# TRS-80_Testboard.net
KiCad netlist of a schematic drawn in EasyEDA
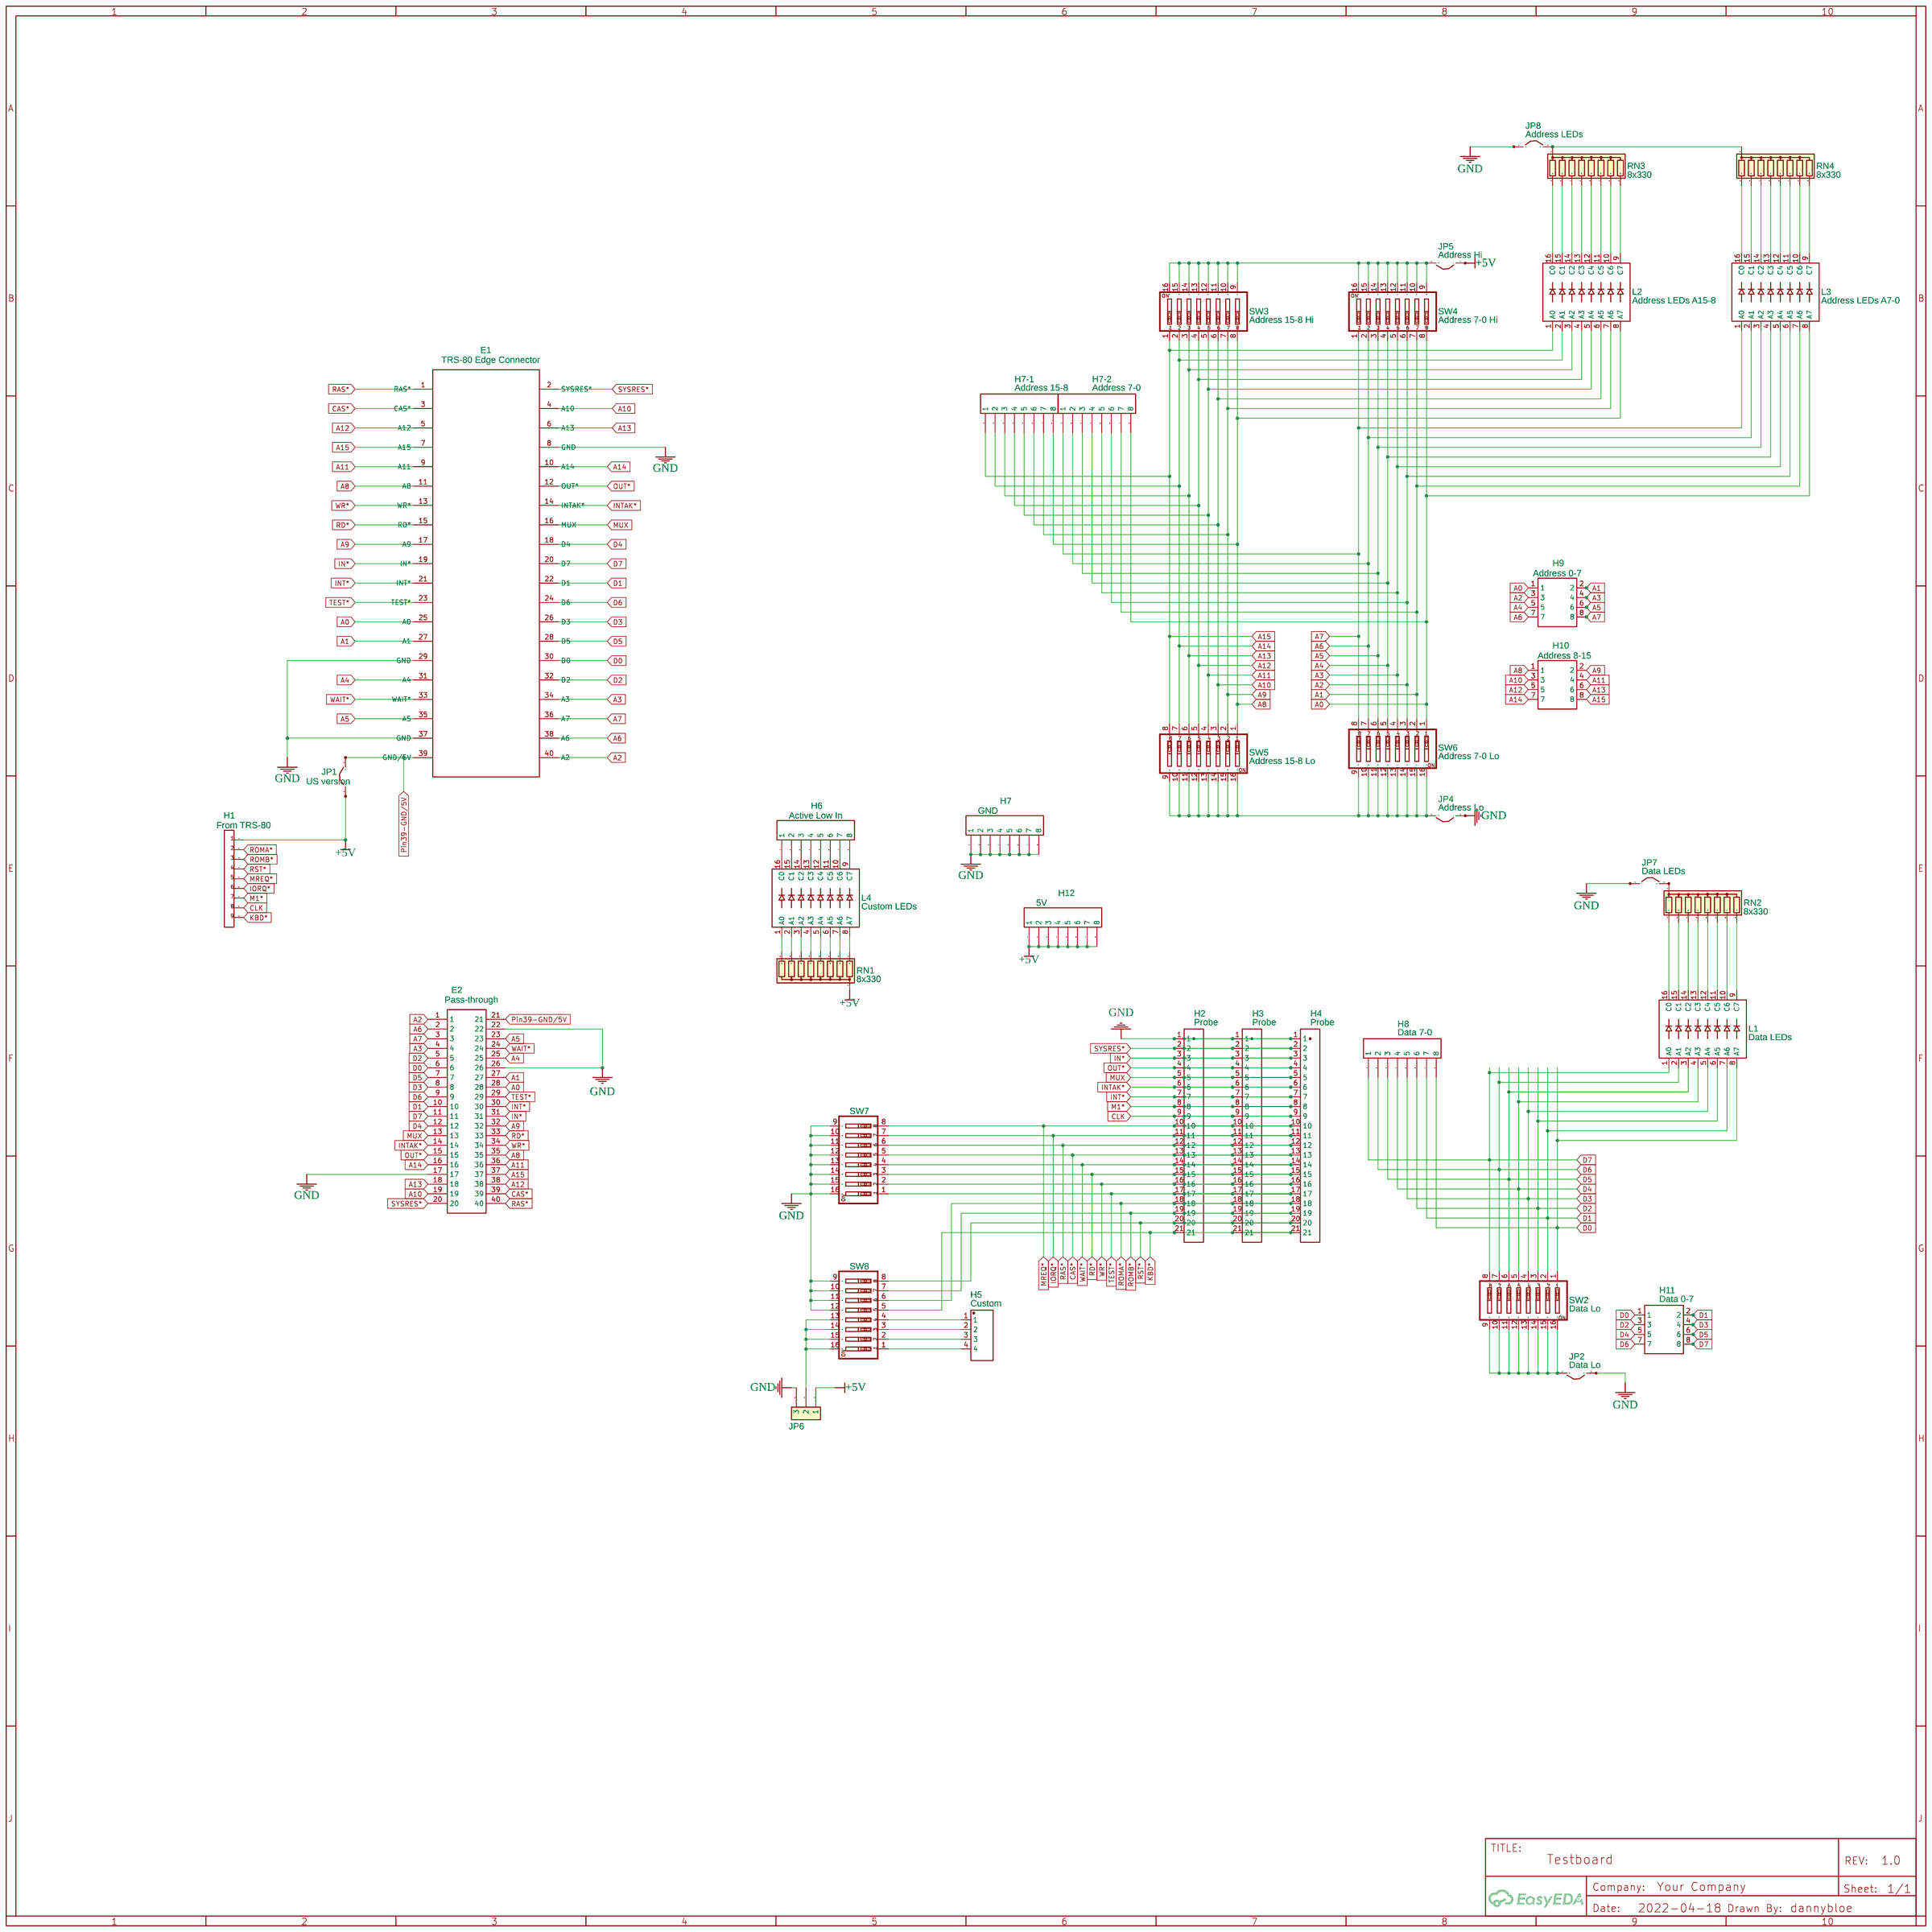
[diagram p0: schematic sheet]

(export (version "E")
  (design (tool "Eeschema 10.0.6"))
  (components
    (comp (ref "E1") (value "TRS-80 Edge Connector") (libsource (lib "") (part "TRS-80 Edge Connector")))
    (comp (ref "E2") (value "Pass-through") (libsource (lib "") (part "40-pos Edge Connector")))
    (comp (ref "H1") (value "From TRS-80") (libsource (lib "") (part "Header1x9_2.54")))
    (comp (ref "H2") (value "Probe") (libsource (lib "") (part "Header 21pin")))
    (comp (ref "H3") (value "Probe") (libsource (lib "") (part "Header 21pin")))
    (comp (ref "H4") (value "Probe") (libsource (lib "") (part "Header 21pin")))
    (comp (ref "H5") (value "Custom") (libsource (lib "") (part "HEADER - HEADER-FEMALE-2.54_1X4")))
    (comp (ref "H6")
      (value "Active Low In")
      (fields
        (field (name "BOM_Manufacturer Part") "Header2.54mm 1*8P")
        (field (name "BOM_Supplier Part") "C49256")
      )
      (libsource (lib "") (part "Header2.54mm 1*8P"))
    )
    (comp (ref "H7")
      (value "GND")
      (fields
        (field (name "BOM_Manufacturer Part") "Header2.54mm 1*8P")
        (field (name "BOM_Supplier Part") "C49256")
      )
      (libsource (lib "") (part "Header2.54mm 1*8P"))
    )
    (comp (ref "H7-1")
      (value "Address 15-8")
      (fields
        (field (name "BOM_Manufacturer Part") "Header2.54mm 1*8P")
        (field (name "BOM_Supplier Part") "C49256")
      )
      (libsource (lib "") (part "Header2.54mm 1*8P_1"))
    )
    (comp (ref "H7-2")
      (value "Address 7-0")
      (fields
        (field (name "BOM_Manufacturer Part") "Header2.54mm 1*8P")
        (field (name "BOM_Supplier Part") "C49256")
      )
      (libsource (lib "") (part "Header2.54mm 1*8P_1"))
    )
    (comp (ref "H8")
      (value "Data 7-0")
      (fields
        (field (name "BOM_Manufacturer Part") "Header2.54mm 1*8P")
        (field (name "BOM_Supplier Part") "C49256")
      )
      (libsource (lib "") (part "Header2.54mm 1*8P"))
    )
    (comp (ref "H9")
      (value "Address 0-7")
      (fields (field (name "BOM_Manufacturer Part") "BKL 10120552"))
      (libsource (lib "") (part "Box Header 8P"))
    )
    (comp (ref "H10")
      (value "Address 8-15")
      (fields (field (name "BOM_Manufacturer Part") "BKL 10120552"))
      (libsource (lib "") (part "Box Header 8P"))
    )
    (comp (ref "H11")
      (value "Data 0-7")
      (fields (field (name "BOM_Manufacturer Part") "BKL 10120552"))
      (libsource (lib "") (part "Box Header 8P"))
    )
    (comp (ref "H12")
      (value "5V")
      (fields
        (field (name "BOM_Manufacturer Part") "Header2.54mm 1*8P")
        (field (name "BOM_Supplier Part") "C49256")
      )
      (libsource (lib "") (part "Header2.54mm 1*8P"))
    )
    (comp (ref "JP1")
      (value "US version")
      (fields (field (name "BOM_Manufacturer Part") "NONE"))
      (libsource (lib "") (part "JUMPERTHRUHOLE_1"))
    )
    (comp (ref "JP2")
      (value "Data Lo")
      (fields (field (name "BOM_Manufacturer Part") "NONE"))
      (libsource (lib "") (part "JUMPERTHRUHOLE_2"))
    )
    (comp (ref "JP4")
      (value "Address Lo")
      (fields (field (name "BOM_Manufacturer Part") "NONE"))
      (libsource (lib "") (part "JUMPERTHRUHOLE_2"))
    )
    (comp (ref "JP5")
      (value "Address Hi")
      (fields (field (name "BOM_Manufacturer Part") "NONE"))
      (libsource (lib "") (part "JUMPERTHRUHOLE_2"))
    )
    (comp (ref "JP6")
      (value "Header1x3")
      (fields
        (field (name "BOM_Manufacturer Part") "Header-Female-2.54_1x10")
        (field (name "BOM_Supplier Part") "C35445")
      )
      (libsource (lib "") (part "Header1x3"))
    )
    (comp (ref "JP7")
      (value "Data LEDs")
      (fields (field (name "BOM_Manufacturer Part") "NONE"))
      (libsource (lib "") (part "JUMPERTHRUHOLE"))
    )
    (comp (ref "JP8")
      (value "Address LEDs")
      (fields (field (name "BOM_Manufacturer Part") "NONE"))
      (libsource (lib "") (part "JUMPERTHRUHOLE"))
    )
    (comp (ref "L1") (value "Data LEDs") (libsource (lib "") (part "BARGRAPH_8")))
    (comp (ref "L2") (value "Address LEDs A15-8") (libsource (lib "") (part "BARGRAPH_8")))
    (comp (ref "L3") (value "Address LEDs A7-0") (libsource (lib "") (part "BARGRAPH_8")))
    (comp (ref "L4") (value "Custom LEDs") (libsource (lib "") (part "BARGRAPH_8")))
    (comp (ref "RN1") (value "8x330") (libsource (lib "") (part "Resistor Network 8")))
    (comp (ref "RN2") (value "8x330") (libsource (lib "") (part "Resistor Network 8_1")))
    (comp (ref "RN3") (value "8x330") (libsource (lib "") (part "Resistor Network 8_1")))
    (comp (ref "RN4") (value "8x330") (libsource (lib "") (part "Resistor Network 8_1")))
    (comp (ref "SW2") (value "Data Lo") (libsource (lib "") (part "SW_DIP-8_3")))
    (comp (ref "SW3") (value "Address 15-8 Hi") (libsource (lib "") (part "SW_DIP-8_2")))
    (comp (ref "SW4") (value "Address 7-0 Hi") (libsource (lib "") (part "SW_DIP-8_2")))
    (comp (ref "SW5") (value "Address 15-8 Lo") (libsource (lib "") (part "SW_DIP-8")))
    (comp (ref "SW6") (value "Address 7-0 Lo") (libsource (lib "") (part "SW_DIP-8")))
    (comp (ref "SW7") (value "Switches") (libsource (lib "") (part "SW_DIP-8_1")))
    (comp (ref "SW8") (value "Switches") (libsource (lib "") (part "SW_DIP-8_1")))
  )
  (nets
    (net (code "1") (name "+5V") (class "Default")
      (node (ref "H1") (pin "1") (pinfunction "1_1") (pintype "unspecified"))
      (node (ref "H12") (pin "1") (pinfunction "1_1") (pintype "input"))
      (node (ref "H12") (pin "2") (pinfunction "2_2") (pintype "input"))
      (node (ref "H12") (pin "3") (pinfunction "3_3") (pintype "input"))
      (node (ref "H12") (pin "4") (pinfunction "4_4") (pintype "input"))
      (node (ref "H12") (pin "5") (pinfunction "5_5") (pintype "input"))
      (node (ref "H12") (pin "6") (pinfunction "6_6") (pintype "input"))
      (node (ref "H12") (pin "7") (pinfunction "7_7") (pintype "input"))
      (node (ref "H12") (pin "8") (pinfunction "8_8") (pintype "input"))
      (node (ref "JP1") (pin "1") (pinfunction "1_1") (pintype "unspecified"))
      (node (ref "JP5") (pin "1") (pinfunction "1_1") (pintype "unspecified"))
      (node (ref "JP6") (pin "1") (pinfunction "1_1") (pintype "input"))
      (node (ref "RN1") (pin "1") (pinfunction "common_1") (pintype "unspecified"))
    )
    (net (code "2") (name "A0") (class "Default")
      (node (ref "E1") (pin "25") (pinfunction "A0_25") (pintype "unspecified"))
      (node (ref "E2") (pin "28") (pinfunction "28_28") (pintype "unspecified"))
      (node (ref "H7-2") (pin "8") (pinfunction "8_8") (pintype "input"))
      (node (ref "H9") (pin "1") (pinfunction "1_1") (pintype "unspecified"))
      (node (ref "L3") (pin "8") (pinfunction "A7_8") (pintype "unspecified"))
      (node (ref "SW4") (pin "8") (pinfunction "8_8") (pintype "bidirectional"))
      (node (ref "SW6") (pin "1") (pinfunction "1_1") (pintype "bidirectional"))
    )
    (net (code "3") (name "A1") (class "Default")
      (node (ref "E1") (pin "27") (pinfunction "A1_27") (pintype "unspecified"))
      (node (ref "E2") (pin "27") (pinfunction "27_27") (pintype "unspecified"))
      (node (ref "H7-2") (pin "7") (pinfunction "7_7") (pintype "input"))
      (node (ref "H9") (pin "2") (pinfunction "2_2") (pintype "unspecified"))
      (node (ref "L3") (pin "7") (pinfunction "A6_7") (pintype "unspecified"))
      (node (ref "SW4") (pin "7") (pinfunction "7_7") (pintype "bidirectional"))
      (node (ref "SW6") (pin "2") (pinfunction "2_2") (pintype "bidirectional"))
    )
    (net (code "4") (name "A2") (class "Default")
      (node (ref "E1") (pin "40") (pinfunction "A2_40") (pintype "unspecified"))
      (node (ref "E2") (pin "1") (pinfunction "1_1") (pintype "unspecified"))
      (node (ref "H7-2") (pin "6") (pinfunction "6_6") (pintype "input"))
      (node (ref "H9") (pin "3") (pinfunction "3_3") (pintype "unspecified"))
      (node (ref "L3") (pin "6") (pinfunction "A5_6") (pintype "unspecified"))
      (node (ref "SW4") (pin "6") (pinfunction "6_6") (pintype "bidirectional"))
      (node (ref "SW6") (pin "3") (pinfunction "3_3") (pintype "bidirectional"))
    )
    (net (code "5") (name "A3") (class "Default")
      (node (ref "E1") (pin "34") (pinfunction "A3_34") (pintype "unspecified"))
      (node (ref "E2") (pin "4") (pinfunction "4_4") (pintype "unspecified"))
      (node (ref "H7-2") (pin "5") (pinfunction "5_5") (pintype "input"))
      (node (ref "H9") (pin "4") (pinfunction "4_4") (pintype "unspecified"))
      (node (ref "L3") (pin "5") (pinfunction "A4_5") (pintype "unspecified"))
      (node (ref "SW4") (pin "5") (pinfunction "5_5") (pintype "bidirectional"))
      (node (ref "SW6") (pin "4") (pinfunction "4_4") (pintype "bidirectional"))
    )
    (net (code "6") (name "A4") (class "Default")
      (node (ref "E1") (pin "31") (pinfunction "A4_31") (pintype "unspecified"))
      (node (ref "E2") (pin "25") (pinfunction "25_25") (pintype "unspecified"))
      (node (ref "H7-2") (pin "4") (pinfunction "4_4") (pintype "input"))
      (node (ref "H9") (pin "5") (pinfunction "5_5") (pintype "unspecified"))
      (node (ref "L3") (pin "4") (pinfunction "A3_4") (pintype "unspecified"))
      (node (ref "SW4") (pin "4") (pinfunction "4_4") (pintype "bidirectional"))
      (node (ref "SW6") (pin "5") (pinfunction "5_5") (pintype "bidirectional"))
    )
    (net (code "7") (name "A5") (class "Default")
      (node (ref "E1") (pin "35") (pinfunction "A5_35") (pintype "unspecified"))
      (node (ref "E2") (pin "23") (pinfunction "23_23") (pintype "unspecified"))
      (node (ref "H7-2") (pin "3") (pinfunction "3_3") (pintype "input"))
      (node (ref "H9") (pin "6") (pinfunction "6_6") (pintype "unspecified"))
      (node (ref "L3") (pin "3") (pinfunction "A2_3") (pintype "unspecified"))
      (node (ref "SW4") (pin "3") (pinfunction "3_3") (pintype "bidirectional"))
      (node (ref "SW6") (pin "6") (pinfunction "6_6") (pintype "bidirectional"))
    )
    (net (code "8") (name "A6") (class "Default")
      (node (ref "E1") (pin "38") (pinfunction "A6_38") (pintype "unspecified"))
      (node (ref "E2") (pin "2") (pinfunction "2_2") (pintype "unspecified"))
      (node (ref "H7-2") (pin "2") (pinfunction "2_2") (pintype "input"))
      (node (ref "H9") (pin "7") (pinfunction "7_7") (pintype "unspecified"))
      (node (ref "L3") (pin "2") (pinfunction "A1_2") (pintype "unspecified"))
      (node (ref "SW4") (pin "2") (pinfunction "2_2") (pintype "bidirectional"))
      (node (ref "SW6") (pin "7") (pinfunction "7_7") (pintype "bidirectional"))
    )
    (net (code "9") (name "A7") (class "Default")
      (node (ref "E1") (pin "36") (pinfunction "A7_36") (pintype "unspecified"))
      (node (ref "E2") (pin "3") (pinfunction "3_3") (pintype "unspecified"))
      (node (ref "H7-2") (pin "1") (pinfunction "1_1") (pintype "input"))
      (node (ref "H9") (pin "8") (pinfunction "8_8") (pintype "unspecified"))
      (node (ref "L3") (pin "1") (pinfunction "A0_1") (pintype "unspecified"))
      (node (ref "SW4") (pin "1") (pinfunction "1_1") (pintype "bidirectional"))
      (node (ref "SW6") (pin "8") (pinfunction "8_8") (pintype "bidirectional"))
    )
    (net (code "10") (name "A8") (class "Default")
      (node (ref "E1") (pin "11") (pinfunction "A8_11") (pintype "unspecified"))
      (node (ref "E2") (pin "35") (pinfunction "35_35") (pintype "unspecified"))
      (node (ref "H10") (pin "1") (pinfunction "1_1") (pintype "unspecified"))
      (node (ref "H7-1") (pin "8") (pinfunction "8_8") (pintype "input"))
      (node (ref "L2") (pin "8") (pinfunction "A7_8") (pintype "unspecified"))
      (node (ref "SW3") (pin "8") (pinfunction "8_8") (pintype "bidirectional"))
      (node (ref "SW5") (pin "1") (pinfunction "1_1") (pintype "bidirectional"))
    )
    (net (code "11") (name "A9") (class "Default")
      (node (ref "E1") (pin "17") (pinfunction "A9_17") (pintype "unspecified"))
      (node (ref "E2") (pin "32") (pinfunction "32_32") (pintype "unspecified"))
      (node (ref "H10") (pin "2") (pinfunction "2_2") (pintype "unspecified"))
      (node (ref "H7-1") (pin "7") (pinfunction "7_7") (pintype "input"))
      (node (ref "L2") (pin "7") (pinfunction "A6_7") (pintype "unspecified"))
      (node (ref "SW3") (pin "7") (pinfunction "7_7") (pintype "bidirectional"))
      (node (ref "SW5") (pin "2") (pinfunction "2_2") (pintype "bidirectional"))
    )
    (net (code "12") (name "A10") (class "Default")
      (node (ref "E1") (pin "4") (pinfunction "A10_4") (pintype "unspecified"))
      (node (ref "E2") (pin "19") (pinfunction "19_19") (pintype "unspecified"))
      (node (ref "H10") (pin "3") (pinfunction "3_3") (pintype "unspecified"))
      (node (ref "H7-1") (pin "6") (pinfunction "6_6") (pintype "input"))
      (node (ref "L2") (pin "6") (pinfunction "A5_6") (pintype "unspecified"))
      (node (ref "SW3") (pin "6") (pinfunction "6_6") (pintype "bidirectional"))
      (node (ref "SW5") (pin "3") (pinfunction "3_3") (pintype "bidirectional"))
    )
    (net (code "13") (name "A11") (class "Default")
      (node (ref "E1") (pin "9") (pinfunction "A11_9") (pintype "unspecified"))
      (node (ref "E2") (pin "36") (pinfunction "36_36") (pintype "unspecified"))
      (node (ref "H10") (pin "4") (pinfunction "4_4") (pintype "unspecified"))
      (node (ref "H7-1") (pin "5") (pinfunction "5_5") (pintype "input"))
      (node (ref "L2") (pin "5") (pinfunction "A4_5") (pintype "unspecified"))
      (node (ref "SW3") (pin "5") (pinfunction "5_5") (pintype "bidirectional"))
      (node (ref "SW5") (pin "4") (pinfunction "4_4") (pintype "bidirectional"))
    )
    (net (code "14") (name "A12") (class "Default")
      (node (ref "E1") (pin "5") (pinfunction "A12_5") (pintype "unspecified"))
      (node (ref "E2") (pin "38") (pinfunction "38_38") (pintype "unspecified"))
      (node (ref "H10") (pin "5") (pinfunction "5_5") (pintype "unspecified"))
      (node (ref "H7-1") (pin "4") (pinfunction "4_4") (pintype "input"))
      (node (ref "L2") (pin "4") (pinfunction "A3_4") (pintype "unspecified"))
      (node (ref "SW3") (pin "4") (pinfunction "4_4") (pintype "bidirectional"))
      (node (ref "SW5") (pin "5") (pinfunction "5_5") (pintype "bidirectional"))
    )
    (net (code "15") (name "A13") (class "Default")
      (node (ref "E1") (pin "6") (pinfunction "A13_6") (pintype "unspecified"))
      (node (ref "E2") (pin "18") (pinfunction "18_18") (pintype "unspecified"))
      (node (ref "H10") (pin "6") (pinfunction "6_6") (pintype "unspecified"))
      (node (ref "H7-1") (pin "3") (pinfunction "3_3") (pintype "input"))
      (node (ref "L2") (pin "3") (pinfunction "A2_3") (pintype "unspecified"))
      (node (ref "SW3") (pin "3") (pinfunction "3_3") (pintype "bidirectional"))
      (node (ref "SW5") (pin "6") (pinfunction "6_6") (pintype "bidirectional"))
    )
    (net (code "16") (name "A14") (class "Default")
      (node (ref "E1") (pin "10") (pinfunction "A14_10") (pintype "unspecified"))
      (node (ref "E2") (pin "16") (pinfunction "16_16") (pintype "unspecified"))
      (node (ref "H10") (pin "7") (pinfunction "7_7") (pintype "unspecified"))
      (node (ref "H7-1") (pin "2") (pinfunction "2_2") (pintype "input"))
      (node (ref "L2") (pin "2") (pinfunction "A1_2") (pintype "unspecified"))
      (node (ref "SW3") (pin "2") (pinfunction "2_2") (pintype "bidirectional"))
      (node (ref "SW5") (pin "7") (pinfunction "7_7") (pintype "bidirectional"))
    )
    (net (code "17") (name "A15") (class "Default")
      (node (ref "E1") (pin "7") (pinfunction "A15_7") (pintype "unspecified"))
      (node (ref "E2") (pin "37") (pinfunction "37_37") (pintype "unspecified"))
      (node (ref "H10") (pin "8") (pinfunction "8_8") (pintype "unspecified"))
      (node (ref "H7-1") (pin "1") (pinfunction "1_1") (pintype "input"))
      (node (ref "L2") (pin "1") (pinfunction "A0_1") (pintype "unspecified"))
      (node (ref "SW3") (pin "1") (pinfunction "1_1") (pintype "bidirectional"))
      (node (ref "SW5") (pin "8") (pinfunction "8_8") (pintype "bidirectional"))
    )
    (net (code "18") (name "CAS*") (class "Default")
      (node (ref "E1") (pin "3") (pinfunction "CAS*_3") (pintype "unspecified"))
      (node (ref "E2") (pin "39") (pinfunction "39_39") (pintype "unspecified"))
      (node (ref "H2") (pin "13") (pinfunction "13_13") (pintype "unspecified"))
      (node (ref "H3") (pin "13") (pinfunction "13_13") (pintype "unspecified"))
      (node (ref "H4") (pin "13") (pinfunction "13_13") (pintype "unspecified"))
      (node (ref "SW7") (pin "5") (pinfunction "5_5") (pintype "bidirectional"))
    )
    (net (code "19") (name "CLK") (class "Default")
      (node (ref "H1") (pin "8") (pinfunction "8_8") (pintype "unspecified"))
      (node (ref "H2") (pin "9") (pinfunction "9_9") (pintype "unspecified"))
      (node (ref "H3") (pin "9") (pinfunction "9_9") (pintype "unspecified"))
      (node (ref "H4") (pin "9") (pinfunction "9_9") (pintype "unspecified"))
    )
    (net (code "20") (name "D0") (class "Default")
      (node (ref "E1") (pin "30") (pinfunction "D0_30") (pintype "unspecified"))
      (node (ref "E2") (pin "6") (pinfunction "6_6") (pintype "unspecified"))
      (node (ref "H11") (pin "1") (pinfunction "1_1") (pintype "unspecified"))
      (node (ref "H8") (pin "8") (pinfunction "8_8") (pintype "input"))
      (node (ref "L1") (pin "8") (pinfunction "A7_8") (pintype "unspecified"))
      (node (ref "SW2") (pin "1") (pinfunction "1_1") (pintype "bidirectional"))
    )
    (net (code "21") (name "D1") (class "Default")
      (node (ref "E1") (pin "22") (pinfunction "D1_22") (pintype "unspecified"))
      (node (ref "E2") (pin "10") (pinfunction "10_10") (pintype "unspecified"))
      (node (ref "H11") (pin "2") (pinfunction "2_2") (pintype "unspecified"))
      (node (ref "H8") (pin "7") (pinfunction "7_7") (pintype "input"))
      (node (ref "L1") (pin "7") (pinfunction "A6_7") (pintype "unspecified"))
      (node (ref "SW2") (pin "2") (pinfunction "2_2") (pintype "bidirectional"))
    )
    (net (code "22") (name "D2") (class "Default")
      (node (ref "E1") (pin "32") (pinfunction "D2_32") (pintype "unspecified"))
      (node (ref "E2") (pin "5") (pinfunction "5_5") (pintype "unspecified"))
      (node (ref "H11") (pin "3") (pinfunction "3_3") (pintype "unspecified"))
      (node (ref "H8") (pin "6") (pinfunction "6_6") (pintype "input"))
      (node (ref "L1") (pin "6") (pinfunction "A5_6") (pintype "unspecified"))
      (node (ref "SW2") (pin "3") (pinfunction "3_3") (pintype "bidirectional"))
    )
    (net (code "23") (name "D3") (class "Default")
      (node (ref "E1") (pin "26") (pinfunction "D3_26") (pintype "unspecified"))
      (node (ref "E2") (pin "8") (pinfunction "8_8") (pintype "unspecified"))
      (node (ref "H11") (pin "4") (pinfunction "4_4") (pintype "unspecified"))
      (node (ref "H8") (pin "5") (pinfunction "5_5") (pintype "input"))
      (node (ref "L1") (pin "5") (pinfunction "A4_5") (pintype "unspecified"))
      (node (ref "SW2") (pin "4") (pinfunction "4_4") (pintype "bidirectional"))
    )
    (net (code "24") (name "D4") (class "Default")
      (node (ref "E1") (pin "18") (pinfunction "D4_18") (pintype "unspecified"))
      (node (ref "E2") (pin "12") (pinfunction "12_12") (pintype "unspecified"))
      (node (ref "H11") (pin "5") (pinfunction "5_5") (pintype "unspecified"))
      (node (ref "H8") (pin "4") (pinfunction "4_4") (pintype "input"))
      (node (ref "L1") (pin "4") (pinfunction "A3_4") (pintype "unspecified"))
      (node (ref "SW2") (pin "5") (pinfunction "5_5") (pintype "bidirectional"))
    )
    (net (code "25") (name "D5") (class "Default")
      (node (ref "E1") (pin "28") (pinfunction "D5_28") (pintype "unspecified"))
      (node (ref "E2") (pin "7") (pinfunction "7_7") (pintype "unspecified"))
      (node (ref "H11") (pin "6") (pinfunction "6_6") (pintype "unspecified"))
      (node (ref "H8") (pin "3") (pinfunction "3_3") (pintype "input"))
      (node (ref "L1") (pin "3") (pinfunction "A2_3") (pintype "unspecified"))
      (node (ref "SW2") (pin "6") (pinfunction "6_6") (pintype "bidirectional"))
    )
    (net (code "26") (name "D6") (class "Default")
      (node (ref "E1") (pin "24") (pinfunction "D6_24") (pintype "unspecified"))
      (node (ref "E2") (pin "9") (pinfunction "9_9") (pintype "unspecified"))
      (node (ref "H11") (pin "7") (pinfunction "7_7") (pintype "unspecified"))
      (node (ref "H8") (pin "2") (pinfunction "2_2") (pintype "input"))
      (node (ref "L1") (pin "2") (pinfunction "A1_2") (pintype "unspecified"))
      (node (ref "SW2") (pin "7") (pinfunction "7_7") (pintype "bidirectional"))
    )
    (net (code "27") (name "D7") (class "Default")
      (node (ref "E1") (pin "20") (pinfunction "D7_20") (pintype "unspecified"))
      (node (ref "E2") (pin "11") (pinfunction "11_11") (pintype "unspecified"))
      (node (ref "H11") (pin "8") (pinfunction "8_8") (pintype "unspecified"))
      (node (ref "H8") (pin "1") (pinfunction "1_1") (pintype "input"))
      (node (ref "L1") (pin "1") (pinfunction "A0_1") (pintype "unspecified"))
      (node (ref "SW2") (pin "8") (pinfunction "8_8") (pintype "bidirectional"))
    )
    (net (code "28") (name "GND") (class "Default")
      (node (ref "E1") (pin "29") (pinfunction "GND_29") (pintype "unspecified"))
      (node (ref "E1") (pin "37") (pinfunction "GND_37") (pintype "unspecified"))
      (node (ref "E1") (pin "8") (pinfunction "GND_8") (pintype "unspecified"))
      (node (ref "E2") (pin "17") (pinfunction "17_17") (pintype "unspecified"))
      (node (ref "E2") (pin "22") (pinfunction "22_22") (pintype "unspecified"))
      (node (ref "E2") (pin "26") (pinfunction "26_26") (pintype "unspecified"))
      (node (ref "H2") (pin "1") (pinfunction "1_1") (pintype "unspecified"))
      (node (ref "H3") (pin "1") (pinfunction "1_1") (pintype "unspecified"))
      (node (ref "H4") (pin "1") (pinfunction "1_1") (pintype "unspecified"))
      (node (ref "H7") (pin "1") (pinfunction "1_1") (pintype "input"))
      (node (ref "H7") (pin "2") (pinfunction "2_2") (pintype "input"))
      (node (ref "H7") (pin "3") (pinfunction "3_3") (pintype "input"))
      (node (ref "H7") (pin "4") (pinfunction "4_4") (pintype "input"))
      (node (ref "H7") (pin "5") (pinfunction "5_5") (pintype "input"))
      (node (ref "H7") (pin "6") (pinfunction "6_6") (pintype "input"))
      (node (ref "H7") (pin "7") (pinfunction "7_7") (pintype "input"))
      (node (ref "H7") (pin "8") (pinfunction "8_8") (pintype "input"))
      (node (ref "JP2") (pin "1") (pinfunction "1_1") (pintype "unspecified"))
      (node (ref "JP4") (pin "1") (pinfunction "1_1") (pintype "unspecified"))
      (node (ref "JP6") (pin "3") (pinfunction "3_3") (pintype "input"))
      (node (ref "JP7") (pin "1") (pinfunction "1_1") (pintype "unspecified"))
      (node (ref "JP8") (pin "1") (pinfunction "1_1") (pintype "unspecified"))
      (node (ref "SW7") (pin "10") (pinfunction "10_10") (pintype "bidirectional"))
      (node (ref "SW7") (pin "11") (pinfunction "11_11") (pintype "bidirectional"))
      (node (ref "SW7") (pin "12") (pinfunction "12_12") (pintype "bidirectional"))
      (node (ref "SW7") (pin "13") (pinfunction "13_13") (pintype "bidirectional"))
      (node (ref "SW7") (pin "14") (pinfunction "14_14") (pintype "bidirectional"))
      (node (ref "SW7") (pin "15") (pinfunction "15_15") (pintype "bidirectional"))
      (node (ref "SW7") (pin "16") (pinfunction "16_16") (pintype "bidirectional"))
      (node (ref "SW7") (pin "9") (pinfunction "9_9") (pintype "bidirectional"))
      (node (ref "SW8") (pin "10") (pinfunction "10_10") (pintype "bidirectional"))
      (node (ref "SW8") (pin "11") (pinfunction "11_11") (pintype "bidirectional"))
      (node (ref "SW8") (pin "12") (pinfunction "12_12") (pintype "bidirectional"))
      (node (ref "SW8") (pin "9") (pinfunction "9_9") (pintype "bidirectional"))
    )
    (net (code "29") (name "IN*") (class "Default")
      (node (ref "E1") (pin "19") (pinfunction "IN*_19") (pintype "unspecified"))
      (node (ref "E2") (pin "31") (pinfunction "31_31") (pintype "unspecified"))
      (node (ref "H2") (pin "3") (pinfunction "3_3") (pintype "unspecified"))
      (node (ref "H3") (pin "3") (pinfunction "3_3") (pintype "unspecified"))
      (node (ref "H4") (pin "3") (pinfunction "3_3") (pintype "unspecified"))
    )
    (net (code "30") (name "INT*") (class "Default")
      (node (ref "E1") (pin "21") (pinfunction "INT*_21") (pintype "unspecified"))
      (node (ref "E2") (pin "30") (pinfunction "30_30") (pintype "unspecified"))
      (node (ref "H2") (pin "7") (pinfunction "7_7") (pintype "unspecified"))
      (node (ref "H3") (pin "7") (pinfunction "7_7") (pintype "unspecified"))
      (node (ref "H4") (pin "7") (pinfunction "7_7") (pintype "unspecified"))
    )
    (net (code "31") (name "INTAK*") (class "Default")
      (node (ref "E1") (pin "14") (pinfunction "INTAK*_14") (pintype "unspecified"))
      (node (ref "E2") (pin "14") (pinfunction "14_14") (pintype "unspecified"))
      (node (ref "H2") (pin "6") (pinfunction "6_6") (pintype "unspecified"))
      (node (ref "H3") (pin "6") (pinfunction "6_6") (pintype "unspecified"))
      (node (ref "H4") (pin "6") (pinfunction "6_6") (pintype "unspecified"))
    )
    (net (code "32") (name "IORQ*") (class "Default")
      (node (ref "H1") (pin "6") (pinfunction "6_6") (pintype "unspecified"))
      (node (ref "H2") (pin "11") (pinfunction "11_11") (pintype "unspecified"))
      (node (ref "H3") (pin "11") (pinfunction "11_11") (pintype "unspecified"))
      (node (ref "H4") (pin "11") (pinfunction "11_11") (pintype "unspecified"))
      (node (ref "SW7") (pin "7") (pinfunction "7_7") (pintype "bidirectional"))
    )
    (net (code "33") (name "KBD*") (class "Default")
      (node (ref "H1") (pin "9") (pinfunction "9_9") (pintype "unspecified"))
      (node (ref "H2") (pin "21") (pinfunction "21_21") (pintype "unspecified"))
      (node (ref "H3") (pin "21") (pinfunction "21_21") (pintype "unspecified"))
      (node (ref "H4") (pin "21") (pinfunction "21_21") (pintype "unspecified"))
      (node (ref "SW8") (pin "5") (pinfunction "5_5") (pintype "bidirectional"))
    )
    (net (code "34") (name "M1*") (class "Default")
      (node (ref "H1") (pin "7") (pinfunction "7_7") (pintype "unspecified"))
      (node (ref "H2") (pin "8") (pinfunction "8_8") (pintype "unspecified"))
      (node (ref "H3") (pin "8") (pinfunction "8_8") (pintype "unspecified"))
      (node (ref "H4") (pin "8") (pinfunction "8_8") (pintype "unspecified"))
    )
    (net (code "35") (name "MREQ*") (class "Default")
      (node (ref "H1") (pin "5") (pinfunction "5_5") (pintype "unspecified"))
      (node (ref "H2") (pin "10") (pinfunction "10_10") (pintype "unspecified"))
      (node (ref "H3") (pin "10") (pinfunction "10_10") (pintype "unspecified"))
      (node (ref "H4") (pin "10") (pinfunction "10_10") (pintype "unspecified"))
      (node (ref "SW7") (pin "8") (pinfunction "8_8") (pintype "bidirectional"))
    )
    (net (code "36") (name "MUX") (class "Default")
      (node (ref "E1") (pin "16") (pinfunction "MUX_16") (pintype "unspecified"))
      (node (ref "E2") (pin "13") (pinfunction "13_13") (pintype "unspecified"))
      (node (ref "H2") (pin "5") (pinfunction "5_5") (pintype "unspecified"))
      (node (ref "H3") (pin "5") (pinfunction "5_5") (pintype "unspecified"))
      (node (ref "H4") (pin "5") (pinfunction "5_5") (pintype "unspecified"))
    )
    (net (code "37") (name "Net-(H5-Pad1)") (class "Default")
      (node (ref "H5") (pin "1") (pinfunction "1_1") (pintype "unspecified"))
      (node (ref "SW8") (pin "4") (pinfunction "4_4") (pintype "bidirectional"))
    )
    (net (code "38") (name "Net-(H5-Pad2)") (class "Default")
      (node (ref "H5") (pin "2") (pinfunction "2_2") (pintype "unspecified"))
      (node (ref "SW8") (pin "3") (pinfunction "3_3") (pintype "bidirectional"))
    )
    (net (code "39") (name "Net-(H5-Pad3)") (class "Default")
      (node (ref "H5") (pin "3") (pinfunction "3_3") (pintype "unspecified"))
      (node (ref "SW8") (pin "2") (pinfunction "2_2") (pintype "bidirectional"))
    )
    (net (code "40") (name "Net-(H5-Pad4)") (class "Default")
      (node (ref "H5") (pin "4") (pinfunction "4_4") (pintype "unspecified"))
      (node (ref "SW8") (pin "1") (pinfunction "1_1") (pintype "bidirectional"))
    )
    (net (code "41") (name "Net-(JP2-Pad2)") (class "Default")
      (node (ref "JP2") (pin "2") (pinfunction "2_2") (pintype "unspecified"))
      (node (ref "SW2") (pin "10") (pinfunction "10_10") (pintype "bidirectional"))
      (node (ref "SW2") (pin "11") (pinfunction "11_11") (pintype "bidirectional"))
      (node (ref "SW2") (pin "12") (pinfunction "12_12") (pintype "bidirectional"))
      (node (ref "SW2") (pin "13") (pinfunction "13_13") (pintype "bidirectional"))
      (node (ref "SW2") (pin "14") (pinfunction "14_14") (pintype "bidirectional"))
      (node (ref "SW2") (pin "15") (pinfunction "15_15") (pintype "bidirectional"))
      (node (ref "SW2") (pin "16") (pinfunction "16_16") (pintype "bidirectional"))
      (node (ref "SW2") (pin "9") (pinfunction "9_9") (pintype "bidirectional"))
    )
    (net (code "42") (name "Net-(JP4-Pad2)") (class "Default")
      (node (ref "JP4") (pin "2") (pinfunction "2_2") (pintype "unspecified"))
      (node (ref "SW5") (pin "10") (pinfunction "10_10") (pintype "bidirectional"))
      (node (ref "SW5") (pin "11") (pinfunction "11_11") (pintype "bidirectional"))
      (node (ref "SW5") (pin "12") (pinfunction "12_12") (pintype "bidirectional"))
      (node (ref "SW5") (pin "13") (pinfunction "13_13") (pintype "bidirectional"))
      (node (ref "SW5") (pin "14") (pinfunction "14_14") (pintype "bidirectional"))
      (node (ref "SW5") (pin "15") (pinfunction "15_15") (pintype "bidirectional"))
      (node (ref "SW5") (pin "16") (pinfunction "16_16") (pintype "bidirectional"))
      (node (ref "SW5") (pin "9") (pinfunction "9_9") (pintype "bidirectional"))
      (node (ref "SW6") (pin "10") (pinfunction "10_10") (pintype "bidirectional"))
      (node (ref "SW6") (pin "11") (pinfunction "11_11") (pintype "bidirectional"))
      (node (ref "SW6") (pin "12") (pinfunction "12_12") (pintype "bidirectional"))
      (node (ref "SW6") (pin "13") (pinfunction "13_13") (pintype "bidirectional"))
      (node (ref "SW6") (pin "14") (pinfunction "14_14") (pintype "bidirectional"))
      (node (ref "SW6") (pin "15") (pinfunction "15_15") (pintype "bidirectional"))
      (node (ref "SW6") (pin "16") (pinfunction "16_16") (pintype "bidirectional"))
      (node (ref "SW6") (pin "9") (pinfunction "9_9") (pintype "bidirectional"))
    )
    (net (code "43") (name "Net-(JP5-Pad2)") (class "Default")
      (node (ref "JP5") (pin "2") (pinfunction "2_2") (pintype "unspecified"))
      (node (ref "SW3") (pin "10") (pinfunction "10_10") (pintype "bidirectional"))
      (node (ref "SW3") (pin "11") (pinfunction "11_11") (pintype "bidirectional"))
      (node (ref "SW3") (pin "12") (pinfunction "12_12") (pintype "bidirectional"))
      (node (ref "SW3") (pin "13") (pinfunction "13_13") (pintype "bidirectional"))
      (node (ref "SW3") (pin "14") (pinfunction "14_14") (pintype "bidirectional"))
      (node (ref "SW3") (pin "15") (pinfunction "15_15") (pintype "bidirectional"))
      (node (ref "SW3") (pin "16") (pinfunction "16_16") (pintype "bidirectional"))
      (node (ref "SW3") (pin "9") (pinfunction "9_9") (pintype "bidirectional"))
      (node (ref "SW4") (pin "10") (pinfunction "10_10") (pintype "bidirectional"))
      (node (ref "SW4") (pin "11") (pinfunction "11_11") (pintype "bidirectional"))
      (node (ref "SW4") (pin "12") (pinfunction "12_12") (pintype "bidirectional"))
      (node (ref "SW4") (pin "13") (pinfunction "13_13") (pintype "bidirectional"))
      (node (ref "SW4") (pin "14") (pinfunction "14_14") (pintype "bidirectional"))
      (node (ref "SW4") (pin "15") (pinfunction "15_15") (pintype "bidirectional"))
      (node (ref "SW4") (pin "16") (pinfunction "16_16") (pintype "bidirectional"))
      (node (ref "SW4") (pin "9") (pinfunction "9_9") (pintype "bidirectional"))
    )
    (net (code "44") (name "Net-(JP6-Pad2)") (class "Default")
      (node (ref "JP6") (pin "2") (pinfunction "2_2") (pintype "input"))
      (node (ref "SW8") (pin "13") (pinfunction "13_13") (pintype "bidirectional"))
      (node (ref "SW8") (pin "14") (pinfunction "14_14") (pintype "bidirectional"))
      (node (ref "SW8") (pin "15") (pinfunction "15_15") (pintype "bidirectional"))
      (node (ref "SW8") (pin "16") (pinfunction "16_16") (pintype "bidirectional"))
    )
    (net (code "45") (name "Net-(L1-C0)") (class "Default")
      (node (ref "L1") (pin "16") (pinfunction "C0_16") (pintype "unspecified"))
      (node (ref "RN2") (pin "2") (pinfunction "R1_2") (pintype "unspecified"))
    )
    (net (code "46") (name "Net-(L1-C1)") (class "Default")
      (node (ref "L1") (pin "15") (pinfunction "C1_15") (pintype "unspecified"))
      (node (ref "RN2") (pin "3") (pinfunction "R2_3") (pintype "unspecified"))
    )
    (net (code "47") (name "Net-(L1-C2)") (class "Default")
      (node (ref "L1") (pin "14") (pinfunction "C2_14") (pintype "unspecified"))
      (node (ref "RN2") (pin "4") (pinfunction "R3_4") (pintype "unspecified"))
    )
    (net (code "48") (name "Net-(L1-C3)") (class "Default")
      (node (ref "L1") (pin "13") (pinfunction "C3_13") (pintype "unspecified"))
      (node (ref "RN2") (pin "5") (pinfunction "R4_5") (pintype "unspecified"))
    )
    (net (code "49") (name "Net-(L1-C4)") (class "Default")
      (node (ref "L1") (pin "12") (pinfunction "C4_12") (pintype "unspecified"))
      (node (ref "RN2") (pin "6") (pinfunction "R5_6") (pintype "unspecified"))
    )
    (net (code "50") (name "Net-(L1-C5)") (class "Default")
      (node (ref "L1") (pin "11") (pinfunction "C5_11") (pintype "unspecified"))
      (node (ref "RN2") (pin "7") (pinfunction "R6_7") (pintype "unspecified"))
    )
    (net (code "51") (name "Net-(L1-C6)") (class "Default")
      (node (ref "L1") (pin "10") (pinfunction "C6_10") (pintype "unspecified"))
      (node (ref "RN2") (pin "8") (pinfunction "R7_8") (pintype "unspecified"))
    )
    (net (code "52") (name "Net-(L1-C7)") (class "Default")
      (node (ref "L1") (pin "9") (pinfunction "C7_9") (pintype "unspecified"))
      (node (ref "RN2") (pin "9") (pinfunction "R8_9") (pintype "unspecified"))
    )
    (net (code "53") (name "Net-(L2-C0)") (class "Default")
      (node (ref "L2") (pin "16") (pinfunction "C0_16") (pintype "unspecified"))
      (node (ref "RN3") (pin "2") (pinfunction "R1_2") (pintype "unspecified"))
    )
    (net (code "54") (name "Net-(L2-C1)") (class "Default")
      (node (ref "L2") (pin "15") (pinfunction "C1_15") (pintype "unspecified"))
      (node (ref "RN3") (pin "3") (pinfunction "R2_3") (pintype "unspecified"))
    )
    (net (code "55") (name "Net-(L2-C2)") (class "Default")
      (node (ref "L2") (pin "14") (pinfunction "C2_14") (pintype "unspecified"))
      (node (ref "RN3") (pin "4") (pinfunction "R3_4") (pintype "unspecified"))
    )
    (net (code "56") (name "Net-(L2-C3)") (class "Default")
      (node (ref "L2") (pin "13") (pinfunction "C3_13") (pintype "unspecified"))
      (node (ref "RN3") (pin "5") (pinfunction "R4_5") (pintype "unspecified"))
    )
    (net (code "57") (name "Net-(L2-C4)") (class "Default")
      (node (ref "L2") (pin "12") (pinfunction "C4_12") (pintype "unspecified"))
      (node (ref "RN3") (pin "6") (pinfunction "R5_6") (pintype "unspecified"))
    )
    (net (code "58") (name "Net-(L2-C5)") (class "Default")
      (node (ref "L2") (pin "11") (pinfunction "C5_11") (pintype "unspecified"))
      (node (ref "RN3") (pin "7") (pinfunction "R6_7") (pintype "unspecified"))
    )
    (net (code "59") (name "Net-(L2-C6)") (class "Default")
      (node (ref "L2") (pin "10") (pinfunction "C6_10") (pintype "unspecified"))
      (node (ref "RN3") (pin "8") (pinfunction "R7_8") (pintype "unspecified"))
    )
    (net (code "60") (name "Net-(L2-C7)") (class "Default")
      (node (ref "L2") (pin "9") (pinfunction "C7_9") (pintype "unspecified"))
      (node (ref "RN3") (pin "9") (pinfunction "R8_9") (pintype "unspecified"))
    )
    (net (code "61") (name "Net-(L3-C0)") (class "Default")
      (node (ref "L3") (pin "16") (pinfunction "C0_16") (pintype "unspecified"))
      (node (ref "RN4") (pin "2") (pinfunction "R1_2") (pintype "unspecified"))
    )
    (net (code "62") (name "Net-(L3-C1)") (class "Default")
      (node (ref "L3") (pin "15") (pinfunction "C1_15") (pintype "unspecified"))
      (node (ref "RN4") (pin "3") (pinfunction "R2_3") (pintype "unspecified"))
    )
    (net (code "63") (name "Net-(L3-C2)") (class "Default")
      (node (ref "L3") (pin "14") (pinfunction "C2_14") (pintype "unspecified"))
      (node (ref "RN4") (pin "4") (pinfunction "R3_4") (pintype "unspecified"))
    )
    (net (code "64") (name "Net-(L3-C3)") (class "Default")
      (node (ref "L3") (pin "13") (pinfunction "C3_13") (pintype "unspecified"))
      (node (ref "RN4") (pin "5") (pinfunction "R4_5") (pintype "unspecified"))
    )
    (net (code "65") (name "Net-(L3-C4)") (class "Default")
      (node (ref "L3") (pin "12") (pinfunction "C4_12") (pintype "unspecified"))
      (node (ref "RN4") (pin "6") (pinfunction "R5_6") (pintype "unspecified"))
    )
    (net (code "66") (name "Net-(L3-C5)") (class "Default")
      (node (ref "L3") (pin "11") (pinfunction "C5_11") (pintype "unspecified"))
      (node (ref "RN4") (pin "7") (pinfunction "R6_7") (pintype "unspecified"))
    )
    (net (code "67") (name "Net-(L3-C6)") (class "Default")
      (node (ref "L3") (pin "10") (pinfunction "C6_10") (pintype "unspecified"))
      (node (ref "RN4") (pin "8") (pinfunction "R7_8") (pintype "unspecified"))
    )
    (net (code "68") (name "Net-(L3-C7)") (class "Default")
      (node (ref "L3") (pin "9") (pinfunction "C7_9") (pintype "unspecified"))
      (node (ref "RN4") (pin "9") (pinfunction "R8_9") (pintype "unspecified"))
    )
    (net (code "69") (name "Net-(L4-A0)") (class "Default")
      (node (ref "L4") (pin "1") (pinfunction "A0_1") (pintype "unspecified"))
      (node (ref "RN1") (pin "9") (pinfunction "R8_9") (pintype "unspecified"))
    )
    (net (code "70") (name "Net-(L4-A1)") (class "Default")
      (node (ref "L4") (pin "2") (pinfunction "A1_2") (pintype "unspecified"))
      (node (ref "RN1") (pin "8") (pinfunction "R7_8") (pintype "unspecified"))
    )
    (net (code "71") (name "Net-(L4-A2)") (class "Default")
      (node (ref "L4") (pin "3") (pinfunction "A2_3") (pintype "unspecified"))
      (node (ref "RN1") (pin "7") (pinfunction "R6_7") (pintype "unspecified"))
    )
    (net (code "72") (name "Net-(L4-A3)") (class "Default")
      (node (ref "L4") (pin "4") (pinfunction "A3_4") (pintype "unspecified"))
      (node (ref "RN1") (pin "6") (pinfunction "R5_6") (pintype "unspecified"))
    )
    (net (code "73") (name "Net-(L4-A4)") (class "Default")
      (node (ref "L4") (pin "5") (pinfunction "A4_5") (pintype "unspecified"))
      (node (ref "RN1") (pin "5") (pinfunction "R4_5") (pintype "unspecified"))
    )
    (net (code "74") (name "Net-(L4-A5)") (class "Default")
      (node (ref "L4") (pin "6") (pinfunction "A5_6") (pintype "unspecified"))
      (node (ref "RN1") (pin "4") (pinfunction "R3_4") (pintype "unspecified"))
    )
    (net (code "75") (name "Net-(L4-A6)") (class "Default")
      (node (ref "L4") (pin "7") (pinfunction "A6_7") (pintype "unspecified"))
      (node (ref "RN1") (pin "3") (pinfunction "R2_3") (pintype "unspecified"))
    )
    (net (code "76") (name "Net-(L4-A7)") (class "Default")
      (node (ref "L4") (pin "8") (pinfunction "A7_8") (pintype "unspecified"))
      (node (ref "RN1") (pin "2") (pinfunction "R1_2") (pintype "unspecified"))
    )
    (net (code "77") (name "Net-(L4-C0)") (class "Default")
      (node (ref "H6") (pin "1") (pinfunction "1_1") (pintype "input"))
      (node (ref "L4") (pin "16") (pinfunction "C0_16") (pintype "unspecified"))
    )
    (net (code "78") (name "Net-(L4-C1)") (class "Default")
      (node (ref "H6") (pin "2") (pinfunction "2_2") (pintype "input"))
      (node (ref "L4") (pin "15") (pinfunction "C1_15") (pintype "unspecified"))
    )
    (net (code "79") (name "Net-(L4-C2)") (class "Default")
      (node (ref "H6") (pin "3") (pinfunction "3_3") (pintype "input"))
      (node (ref "L4") (pin "14") (pinfunction "C2_14") (pintype "unspecified"))
    )
    (net (code "80") (name "Net-(L4-C3)") (class "Default")
      (node (ref "H6") (pin "4") (pinfunction "4_4") (pintype "input"))
      (node (ref "L4") (pin "13") (pinfunction "C3_13") (pintype "unspecified"))
    )
    (net (code "81") (name "Net-(L4-C4)") (class "Default")
      (node (ref "H6") (pin "5") (pinfunction "5_5") (pintype "input"))
      (node (ref "L4") (pin "12") (pinfunction "C4_12") (pintype "unspecified"))
    )
    (net (code "82") (name "Net-(L4-C5)") (class "Default")
      (node (ref "H6") (pin "6") (pinfunction "6_6") (pintype "input"))
      (node (ref "L4") (pin "11") (pinfunction "C5_11") (pintype "unspecified"))
    )
    (net (code "83") (name "Net-(L4-C6)") (class "Default")
      (node (ref "H6") (pin "7") (pinfunction "7_7") (pintype "input"))
      (node (ref "L4") (pin "10") (pinfunction "C6_10") (pintype "unspecified"))
    )
    (net (code "84") (name "Net-(L4-C7)") (class "Default")
      (node (ref "H6") (pin "8") (pinfunction "8_8") (pintype "input"))
      (node (ref "L4") (pin "9") (pinfunction "C7_9") (pintype "unspecified"))
    )
    (net (code "85") (name "Net-(RN2-common)") (class "Default")
      (node (ref "JP7") (pin "2") (pinfunction "2_2") (pintype "unspecified"))
      (node (ref "RN2") (pin "1") (pinfunction "common_1") (pintype "unspecified"))
    )
    (net (code "86") (name "Net-(RN3-common)") (class "Default")
      (node (ref "JP8") (pin "2") (pinfunction "2_2") (pintype "unspecified"))
      (node (ref "RN3") (pin "1") (pinfunction "common_1") (pintype "unspecified"))
      (node (ref "RN4") (pin "1") (pinfunction "common_1") (pintype "unspecified"))
    )
    (net (code "87") (name "OUT*") (class "Default")
      (node (ref "E1") (pin "12") (pinfunction "OUT*_12") (pintype "unspecified"))
      (node (ref "E2") (pin "15") (pinfunction "15_15") (pintype "unspecified"))
      (node (ref "H2") (pin "4") (pinfunction "4_4") (pintype "unspecified"))
      (node (ref "H3") (pin "4") (pinfunction "4_4") (pintype "unspecified"))
      (node (ref "H4") (pin "4") (pinfunction "4_4") (pintype "unspecified"))
    )
    (net (code "88") (name "Pin39-GND{slash}5V") (class "Default")
      (node (ref "E1") (pin "39") (pinfunction "GND/5V_39") (pintype "unspecified"))
      (node (ref "E2") (pin "21") (pinfunction "21_21") (pintype "unspecified"))
      (node (ref "JP1") (pin "2") (pinfunction "2_2") (pintype "unspecified"))
    )
    (net (code "89") (name "RAS*") (class "Default")
      (node (ref "E1") (pin "1") (pinfunction "RAS*_1") (pintype "unspecified"))
      (node (ref "E2") (pin "40") (pinfunction "40_40") (pintype "unspecified"))
      (node (ref "H2") (pin "12") (pinfunction "12_12") (pintype "unspecified"))
      (node (ref "H3") (pin "12") (pinfunction "12_12") (pintype "unspecified"))
      (node (ref "H4") (pin "12") (pinfunction "12_12") (pintype "unspecified"))
      (node (ref "SW7") (pin "6") (pinfunction "6_6") (pintype "bidirectional"))
    )
    (net (code "90") (name "RD*") (class "Default")
      (node (ref "E1") (pin "15") (pinfunction "RD*_15") (pintype "unspecified"))
      (node (ref "E2") (pin "33") (pinfunction "33_33") (pintype "unspecified"))
      (node (ref "H2") (pin "15") (pinfunction "15_15") (pintype "unspecified"))
      (node (ref "H3") (pin "15") (pinfunction "15_15") (pintype "unspecified"))
      (node (ref "H4") (pin "15") (pinfunction "15_15") (pintype "unspecified"))
      (node (ref "SW7") (pin "3") (pinfunction "3_3") (pintype "bidirectional"))
    )
    (net (code "91") (name "ROMA*") (class "Default")
      (node (ref "H1") (pin "2") (pinfunction "2_2") (pintype "unspecified"))
      (node (ref "H2") (pin "18") (pinfunction "18_18") (pintype "unspecified"))
      (node (ref "H3") (pin "18") (pinfunction "18_18") (pintype "unspecified"))
      (node (ref "H4") (pin "18") (pinfunction "18_18") (pintype "unspecified"))
      (node (ref "SW8") (pin "6") (pinfunction "6_6") (pintype "bidirectional"))
    )
    (net (code "92") (name "ROMB*") (class "Default")
      (node (ref "H1") (pin "3") (pinfunction "3_3") (pintype "unspecified"))
      (node (ref "H2") (pin "19") (pinfunction "19_19") (pintype "unspecified"))
      (node (ref "H3") (pin "19") (pinfunction "19_19") (pintype "unspecified"))
      (node (ref "H4") (pin "19") (pinfunction "19_19") (pintype "unspecified"))
      (node (ref "SW8") (pin "7") (pinfunction "7_7") (pintype "bidirectional"))
    )
    (net (code "93") (name "RST*") (class "Default")
      (node (ref "H1") (pin "4") (pinfunction "4_4") (pintype "unspecified"))
      (node (ref "H2") (pin "20") (pinfunction "20_20") (pintype "unspecified"))
      (node (ref "H3") (pin "20") (pinfunction "20_20") (pintype "unspecified"))
      (node (ref "H4") (pin "20") (pinfunction "20_20") (pintype "unspecified"))
      (node (ref "SW8") (pin "8") (pinfunction "8_8") (pintype "bidirectional"))
    )
    (net (code "94") (name "SYSRES*") (class "Default")
      (node (ref "E1") (pin "2") (pinfunction "SYSRES*_2") (pintype "unspecified"))
      (node (ref "E2") (pin "20") (pinfunction "20_20") (pintype "unspecified"))
      (node (ref "H2") (pin "2") (pinfunction "2_2") (pintype "unspecified"))
      (node (ref "H3") (pin "2") (pinfunction "2_2") (pintype "unspecified"))
      (node (ref "H4") (pin "2") (pinfunction "2_2") (pintype "unspecified"))
    )
    (net (code "95") (name "TEST*") (class "Default")
      (node (ref "E1") (pin "23") (pinfunction "TEST*_23") (pintype "unspecified"))
      (node (ref "E2") (pin "29") (pinfunction "29_29") (pintype "unspecified"))
      (node (ref "H2") (pin "17") (pinfunction "17_17") (pintype "unspecified"))
      (node (ref "H3") (pin "17") (pinfunction "17_17") (pintype "unspecified"))
      (node (ref "H4") (pin "17") (pinfunction "17_17") (pintype "unspecified"))
      (node (ref "SW7") (pin "1") (pinfunction "1_1") (pintype "bidirectional"))
    )
    (net (code "96") (name "WAIT*") (class "Default")
      (node (ref "E1") (pin "33") (pinfunction "WAIT*_33") (pintype "unspecified"))
      (node (ref "E2") (pin "24") (pinfunction "24_24") (pintype "unspecified"))
      (node (ref "H2") (pin "14") (pinfunction "14_14") (pintype "unspecified"))
      (node (ref "H3") (pin "14") (pinfunction "14_14") (pintype "unspecified"))
      (node (ref "H4") (pin "14") (pinfunction "14_14") (pintype "unspecified"))
      (node (ref "SW7") (pin "4") (pinfunction "4_4") (pintype "bidirectional"))
    )
    (net (code "97") (name "WR*") (class "Default")
      (node (ref "E1") (pin "13") (pinfunction "WR*_13") (pintype "unspecified"))
      (node (ref "E2") (pin "34") (pinfunction "34_34") (pintype "unspecified"))
      (node (ref "H2") (pin "16") (pinfunction "16_16") (pintype "unspecified"))
      (node (ref "H3") (pin "16") (pinfunction "16_16") (pintype "unspecified"))
      (node (ref "H4") (pin "16") (pinfunction "16_16") (pintype "unspecified"))
      (node (ref "SW7") (pin "2") (pinfunction "2_2") (pintype "bidirectional"))
    )
  )
)
